# power-board-sss.net
KiCad netlist of a schematic drawn in EAGLE
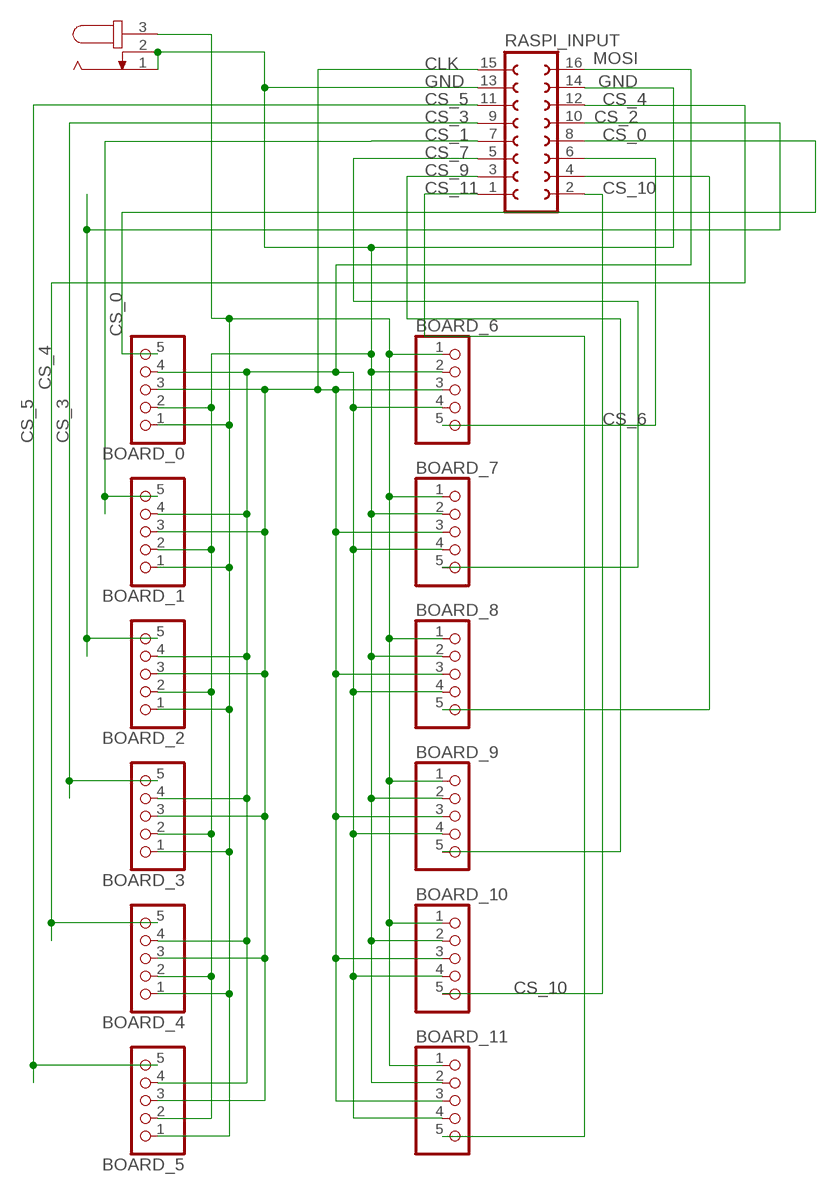
[diagram p0: schematic, sheet 1]

(export (version "E")
  (design (tool "Eeschema 10.0.6"))
  (components
    (comp (ref "BOARD_0")
      (value "PINHD-1X5")
      (footprint "eagle-import:1X05")
      (libsource (lib "eagle-import") (part "PINHD-1X5"))
    )
    (comp (ref "BOARD_1")
      (value "PINHD-1X5")
      (footprint "eagle-import:1X05")
      (libsource (lib "eagle-import") (part "PINHD-1X5"))
    )
    (comp (ref "BOARD_2")
      (value "PINHD-1X5")
      (footprint "eagle-import:1X05")
      (libsource (lib "eagle-import") (part "PINHD-1X5"))
    )
    (comp (ref "BOARD_3")
      (value "PINHD-1X5")
      (footprint "eagle-import:1X05")
      (libsource (lib "eagle-import") (part "PINHD-1X5"))
    )
    (comp (ref "BOARD_4")
      (value "PINHD-1X5")
      (footprint "eagle-import:1X05")
      (libsource (lib "eagle-import") (part "PINHD-1X5"))
    )
    (comp (ref "BOARD_5")
      (value "PINHD-1X5")
      (footprint "eagle-import:1X05")
      (libsource (lib "eagle-import") (part "PINHD-1X5"))
    )
    (comp (ref "BOARD_6")
      (value "PINHD-1X5")
      (footprint "eagle-import:1X05")
      (libsource (lib "eagle-import") (part "PINHD-1X5"))
    )
    (comp (ref "BOARD_7")
      (value "PINHD-1X5")
      (footprint "eagle-import:1X05")
      (libsource (lib "eagle-import") (part "PINHD-1X5"))
    )
    (comp (ref "BOARD_8")
      (value "PINHD-1X5")
      (footprint "eagle-import:1X05")
      (libsource (lib "eagle-import") (part "PINHD-1X5"))
    )
    (comp (ref "BOARD_9")
      (value "PINHD-1X5")
      (footprint "eagle-import:1X05")
      (libsource (lib "eagle-import") (part "PINHD-1X5"))
    )
    (comp (ref "BOARD_10")
      (value "PINHD-1X5")
      (footprint "eagle-import:1X05")
      (libsource (lib "eagle-import") (part "PINHD-1X5"))
    )
    (comp (ref "BOARD_11")
      (value "PINHD-1X5")
      (footprint "eagle-import:1X05")
      (libsource (lib "eagle-import") (part "PINHD-1X5"))
    )
    (comp (ref "J1")
      (value "JACK-PLUG1")
      (footprint "eagle-import:SPC4078")
      (libsource (lib "eagle-import") (part "JACK-PLUG1"))
    )
    (comp (ref "RASPI_INPUT")
      (value "FE08-2")
      (footprint "eagle-import:FE08-2")
      (libsource (lib "eagle-import") (part "FE08-2"))
    )
  )
  (nets
    (net (code "1") (name "/CLK") (class "Default")
      (node (ref "BOARD_0") (pin "3") (pinfunction "3_3") (pintype "passive"))
      (node (ref "BOARD_1") (pin "3") (pinfunction "3_3") (pintype "passive"))
      (node (ref "BOARD_10") (pin "3") (pinfunction "3_3") (pintype "passive"))
      (node (ref "BOARD_11") (pin "3") (pinfunction "3_3") (pintype "passive"))
      (node (ref "BOARD_2") (pin "3") (pinfunction "3_3") (pintype "passive"))
      (node (ref "BOARD_3") (pin "3") (pinfunction "3_3") (pintype "passive"))
      (node (ref "BOARD_4") (pin "3") (pinfunction "3_3") (pintype "passive"))
      (node (ref "BOARD_5") (pin "3") (pinfunction "3_3") (pintype "passive"))
      (node (ref "BOARD_6") (pin "3") (pinfunction "3_3") (pintype "passive"))
      (node (ref "BOARD_7") (pin "3") (pinfunction "3_3") (pintype "passive"))
      (node (ref "BOARD_8") (pin "3") (pinfunction "3_3") (pintype "passive"))
      (node (ref "BOARD_9") (pin "3") (pinfunction "3_3") (pintype "passive"))
      (node (ref "RASPI_INPUT") (pin "15") (pinfunction "15_15") (pintype "passive"))
    )
    (net (code "2") (name "/CS_0") (class "Default")
      (node (ref "BOARD_0") (pin "5") (pinfunction "5_5") (pintype "passive"))
      (node (ref "RASPI_INPUT") (pin "8") (pinfunction "8_8") (pintype "passive"))
    )
    (net (code "3") (name "/CS_1") (class "Default")
      (node (ref "BOARD_1") (pin "5") (pinfunction "5_5") (pintype "passive"))
      (node (ref "RASPI_INPUT") (pin "7") (pinfunction "7_7") (pintype "passive"))
    )
    (net (code "4") (name "/CS_2") (class "Default")
      (node (ref "BOARD_2") (pin "5") (pinfunction "5_5") (pintype "passive"))
      (node (ref "RASPI_INPUT") (pin "10") (pinfunction "10_10") (pintype "passive"))
    )
    (net (code "5") (name "/CS_3") (class "Default")
      (node (ref "BOARD_3") (pin "5") (pinfunction "5_5") (pintype "passive"))
      (node (ref "RASPI_INPUT") (pin "9") (pinfunction "9_9") (pintype "passive"))
    )
    (net (code "6") (name "/CS_4") (class "Default")
      (node (ref "BOARD_4") (pin "5") (pinfunction "5_5") (pintype "passive"))
      (node (ref "RASPI_INPUT") (pin "12") (pinfunction "12_12") (pintype "passive"))
    )
    (net (code "7") (name "/CS_5") (class "Default")
      (node (ref "BOARD_5") (pin "5") (pinfunction "5_5") (pintype "passive"))
      (node (ref "RASPI_INPUT") (pin "11") (pinfunction "11_11") (pintype "passive"))
    )
    (net (code "8") (name "/CS_6") (class "Default")
      (node (ref "BOARD_6") (pin "5") (pinfunction "5_5") (pintype "passive"))
      (node (ref "RASPI_INPUT") (pin "6") (pinfunction "6_6") (pintype "passive"))
    )
    (net (code "9") (name "/CS_7") (class "Default")
      (node (ref "BOARD_7") (pin "5") (pinfunction "5_5") (pintype "passive"))
      (node (ref "RASPI_INPUT") (pin "5") (pinfunction "5_5") (pintype "passive"))
    )
    (net (code "10") (name "/CS_9") (class "Default")
      (node (ref "BOARD_9") (pin "5") (pinfunction "5_5") (pintype "passive"))
      (node (ref "RASPI_INPUT") (pin "3") (pinfunction "3_3") (pintype "passive"))
    )
    (net (code "11") (name "/CS_10") (class "Default")
      (node (ref "BOARD_10") (pin "5") (pinfunction "5_5") (pintype "passive"))
      (node (ref "RASPI_INPUT") (pin "2") (pinfunction "2_2") (pintype "passive"))
    )
    (net (code "12") (name "/CS_11") (class "Default")
      (node (ref "BOARD_11") (pin "5") (pinfunction "5_5") (pintype "passive"))
      (node (ref "RASPI_INPUT") (pin "1") (pinfunction "1_1") (pintype "passive"))
    )
    (net (code "13") (name "/GND") (class "Default")
      (node (ref "BOARD_0") (pin "2") (pinfunction "2_2") (pintype "passive"))
      (node (ref "BOARD_1") (pin "2") (pinfunction "2_2") (pintype "passive"))
      (node (ref "BOARD_10") (pin "2") (pinfunction "2_2") (pintype "passive"))
      (node (ref "BOARD_11") (pin "2") (pinfunction "2_2") (pintype "passive"))
      (node (ref "BOARD_2") (pin "2") (pinfunction "2_2") (pintype "passive"))
      (node (ref "BOARD_3") (pin "2") (pinfunction "2_2") (pintype "passive"))
      (node (ref "BOARD_4") (pin "2") (pinfunction "2_2") (pintype "passive"))
      (node (ref "BOARD_5") (pin "2") (pinfunction "2_2") (pintype "passive"))
      (node (ref "BOARD_6") (pin "2") (pinfunction "2_2") (pintype "passive"))
      (node (ref "BOARD_7") (pin "2") (pinfunction "2_2") (pintype "passive"))
      (node (ref "BOARD_8") (pin "2") (pinfunction "2_2") (pintype "passive"))
      (node (ref "BOARD_9") (pin "2") (pinfunction "2_2") (pintype "passive"))
      (node (ref "J1") (pin "1") (pinfunction "1_1") (pintype "passive"))
      (node (ref "J1") (pin "2") (pinfunction "2_2") (pintype "passive"))
      (node (ref "RASPI_INPUT") (pin "13") (pinfunction "13_13") (pintype "passive"))
      (node (ref "RASPI_INPUT") (pin "14") (pinfunction "14_14") (pintype "passive"))
    )
    (net (code "14") (name "/MOSI") (class "Default")
      (node (ref "BOARD_0") (pin "4") (pinfunction "4_4") (pintype "passive"))
      (node (ref "BOARD_1") (pin "4") (pinfunction "4_4") (pintype "passive"))
      (node (ref "BOARD_10") (pin "4") (pinfunction "4_4") (pintype "passive"))
      (node (ref "BOARD_11") (pin "4") (pinfunction "4_4") (pintype "passive"))
      (node (ref "BOARD_2") (pin "4") (pinfunction "4_4") (pintype "passive"))
      (node (ref "BOARD_3") (pin "4") (pinfunction "4_4") (pintype "passive"))
      (node (ref "BOARD_4") (pin "4") (pinfunction "4_4") (pintype "passive"))
      (node (ref "BOARD_5") (pin "4") (pinfunction "4_4") (pintype "passive"))
      (node (ref "BOARD_6") (pin "4") (pinfunction "4_4") (pintype "passive"))
      (node (ref "BOARD_7") (pin "4") (pinfunction "4_4") (pintype "passive"))
      (node (ref "BOARD_8") (pin "4") (pinfunction "4_4") (pintype "passive"))
      (node (ref "BOARD_9") (pin "4") (pinfunction "4_4") (pintype "passive"))
      (node (ref "RASPI_INPUT") (pin "16") (pinfunction "16_16") (pintype "passive"))
    )
    (net (code "15") (name "Net-(BOARD_0-Pad1)") (class "Default")
      (node (ref "BOARD_0") (pin "1") (pinfunction "1_1") (pintype "passive"))
      (node (ref "BOARD_1") (pin "1") (pinfunction "1_1") (pintype "passive"))
      (node (ref "BOARD_10") (pin "1") (pinfunction "1_1") (pintype "passive"))
      (node (ref "BOARD_11") (pin "1") (pinfunction "1_1") (pintype "passive"))
      (node (ref "BOARD_2") (pin "1") (pinfunction "1_1") (pintype "passive"))
      (node (ref "BOARD_3") (pin "1") (pinfunction "1_1") (pintype "passive"))
      (node (ref "BOARD_4") (pin "1") (pinfunction "1_1") (pintype "passive"))
      (node (ref "BOARD_5") (pin "1") (pinfunction "1_1") (pintype "passive"))
      (node (ref "BOARD_6") (pin "1") (pinfunction "1_1") (pintype "passive"))
      (node (ref "BOARD_7") (pin "1") (pinfunction "1_1") (pintype "passive"))
      (node (ref "BOARD_8") (pin "1") (pinfunction "1_1") (pintype "passive"))
      (node (ref "BOARD_9") (pin "1") (pinfunction "1_1") (pintype "passive"))
      (node (ref "J1") (pin "3") (pinfunction "3_3") (pintype "passive"))
    )
    (net (code "16") (name "Net-(BOARD_8-Pad5)") (class "Default")
      (node (ref "BOARD_8") (pin "5") (pinfunction "5_5") (pintype "passive"))
      (node (ref "RASPI_INPUT") (pin "4") (pinfunction "4_4") (pintype "passive"))
    )
  )
)
